# nerves_key2.net
KiCad netlist of a schematic drawn in EAGLE
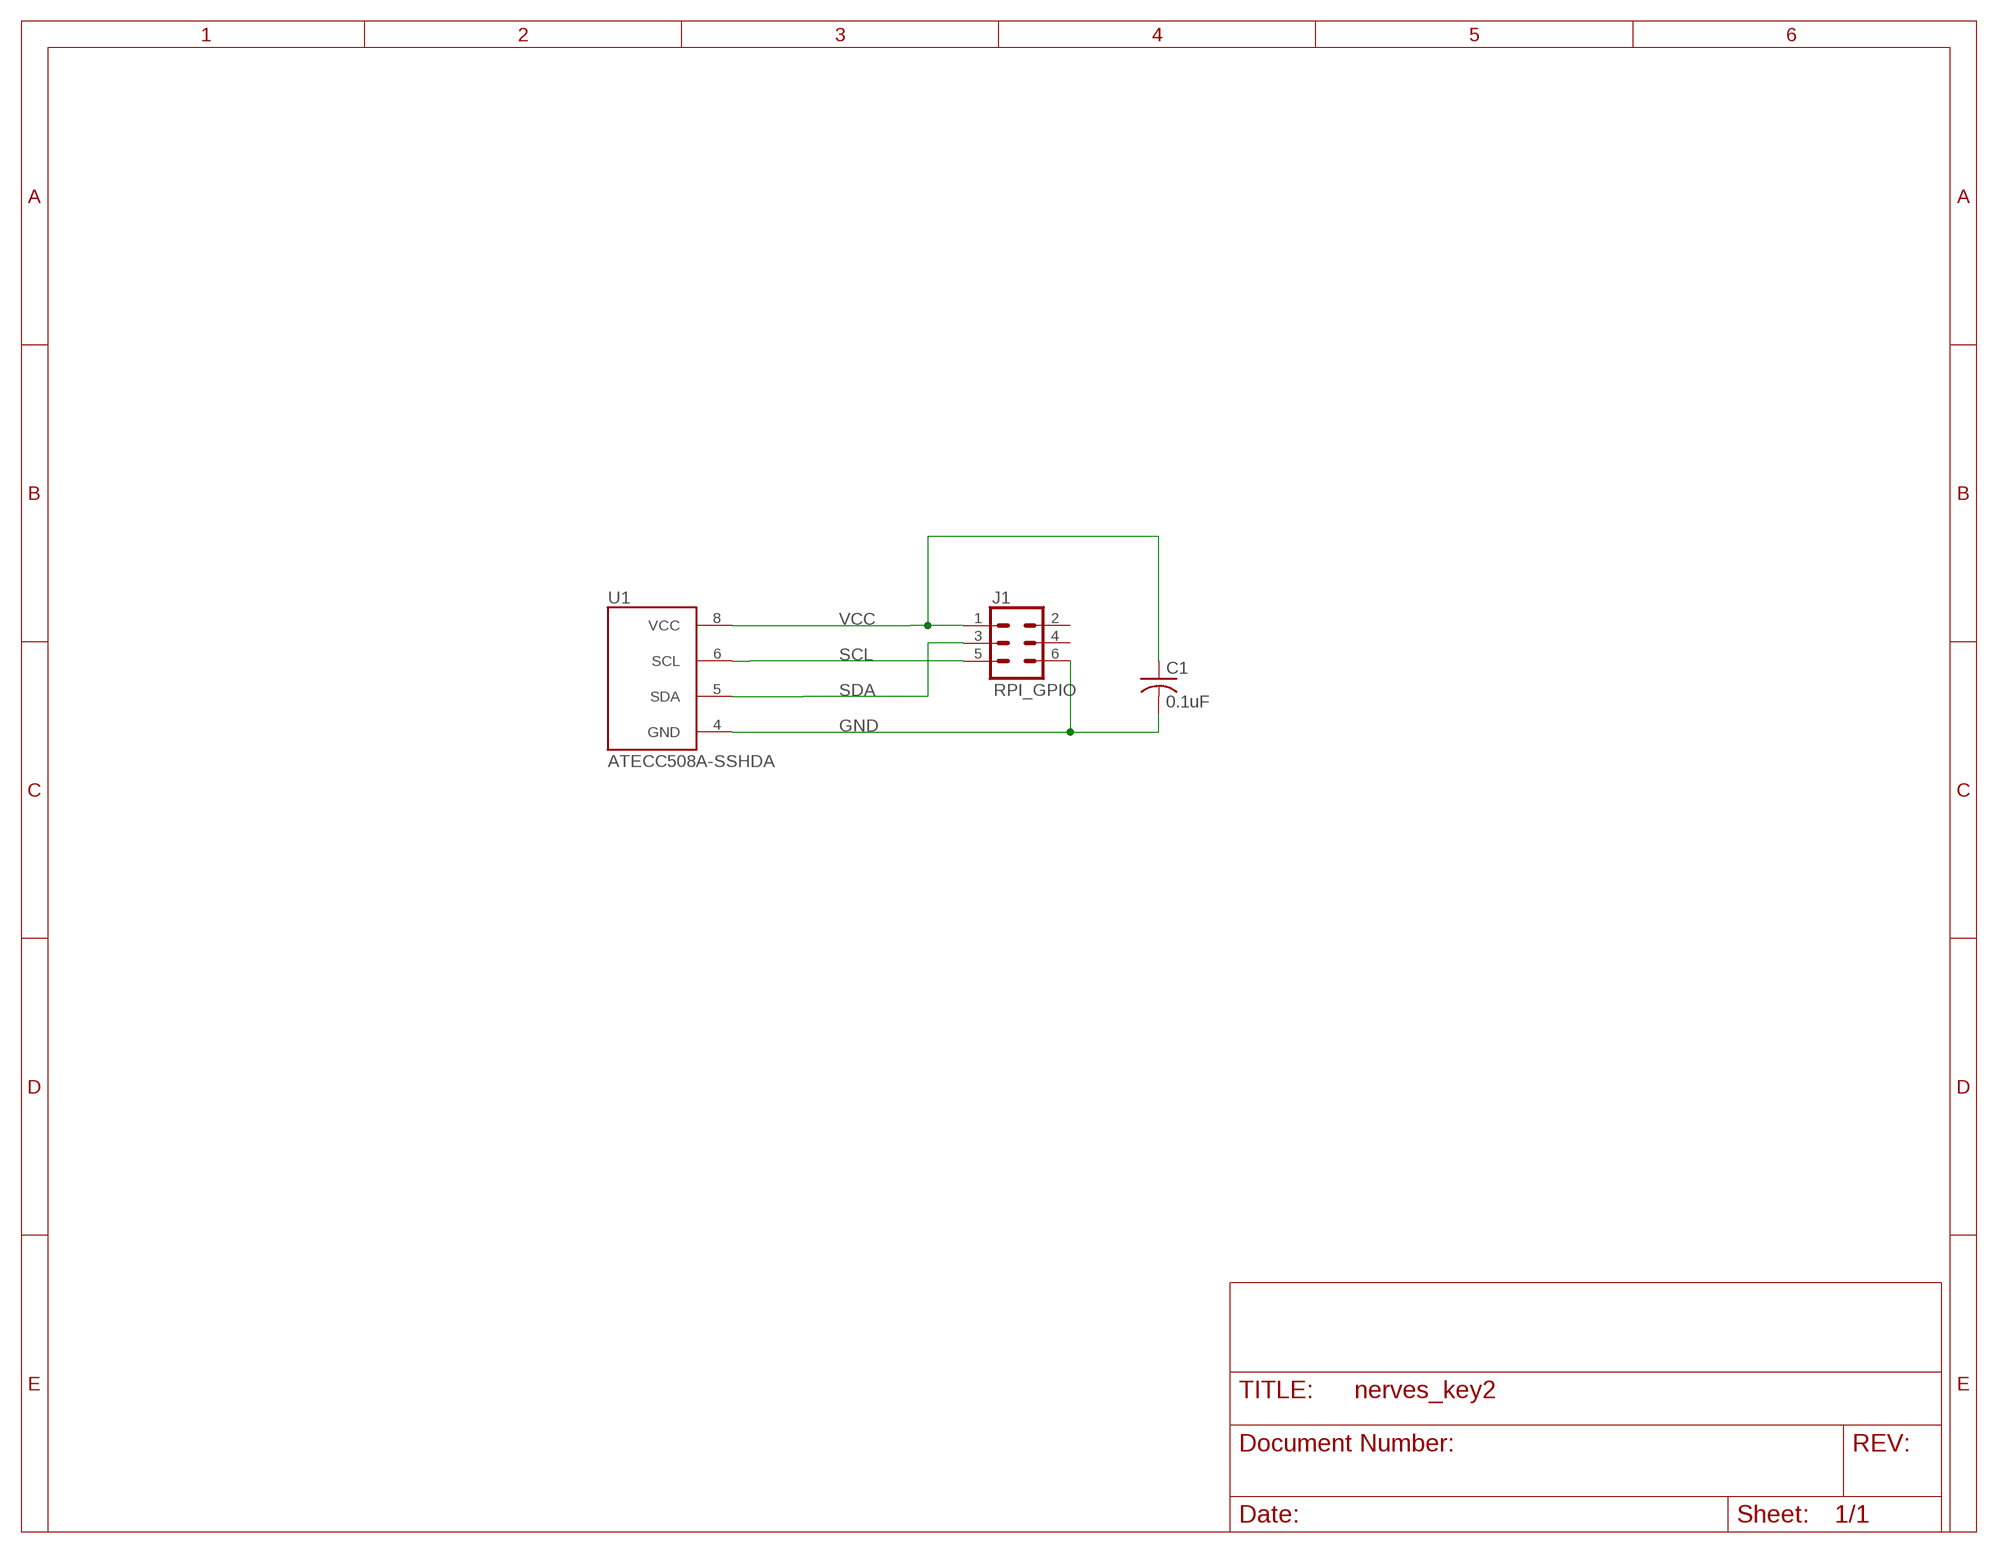
[diagram p0: schematic, sheet 1]

(export (version "E")
  (design (tool "Eeschema 10.0.6"))
  (components
    (comp (ref "C1")
      (value "0.1uF")
      (footprint "eagle-import:C0805")
      (libsource (lib "eagle-import") (part "C-USC0805"))
    )
    (comp (ref "J1")
      (value "RPI_GPIO")
      (footprint "eagle-import:2X3_TIGHT")
      (libsource (lib "eagle-import") (part "CONN_03X2_TIGHT2X3_SILK_MALE_PTH"))
    )
    (comp (ref "U1")
      (value "ATECC508A-SSHDA")
      (footprint "eagle-import:SOIC127P625X175-8")
      (libsource (lib "eagle-import") (part "ATECC508ASOIC-8-NARROW"))
    )
  )
  (nets
    (net (code "1") (name "/GND") (class "Default")
      (node (ref "C1") (pin "2") (pinfunction "2_2") (pintype "passive"))
      (node (ref "J1") (pin "6") (pinfunction "6_6") (pintype "bidirectional"))
      (node (ref "U1") (pin "4") (pinfunction "GND_4") (pintype "bidirectional"))
    )
    (net (code "2") (name "/SCL") (class "Default")
      (node (ref "J1") (pin "5") (pinfunction "5_5") (pintype "bidirectional"))
      (node (ref "U1") (pin "6") (pinfunction "SCL_6") (pintype "bidirectional"))
    )
    (net (code "3") (name "/SDA") (class "Default")
      (node (ref "J1") (pin "3") (pinfunction "3_3") (pintype "bidirectional"))
      (node (ref "U1") (pin "5") (pinfunction "SDA_5") (pintype "bidirectional"))
    )
    (net (code "4") (name "/VCC") (class "Default")
      (node (ref "C1") (pin "1") (pinfunction "1_1") (pintype "passive"))
      (node (ref "J1") (pin "1") (pinfunction "1_1") (pintype "bidirectional"))
      (node (ref "U1") (pin "8") (pinfunction "VCC_8") (pintype "bidirectional"))
    )
    (net (code "5") (name "unconnected-(J1-Pad2)") (class "Default")
      (node (ref "J1") (pin "2") (pinfunction "2_2") (pintype "bidirectional"))
    )
    (net (code "6") (name "unconnected-(J1-Pad4)") (class "Default")
      (node (ref "J1") (pin "4") (pinfunction "4_4") (pintype "bidirectional"))
    )
  )
)
